# DDR4_MotherboardV2.net
KiCad netlist of a schematic drawn in Altium Designer
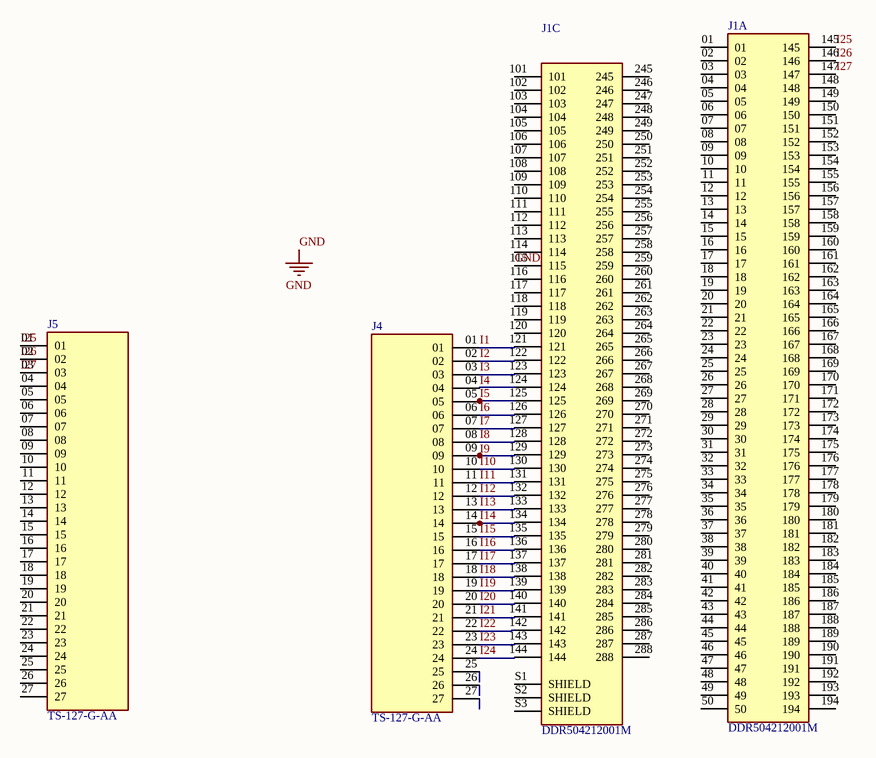
[diagram p0: DDR4_MotherboardV2.SchDoc]

(export (version "E")
  (design (tool "Eeschema 10.0.6"))
  (components
    (comp (ref "J1")
      (value "DDR504212001M")
      (footprint "AMPHENOL_DDR504212001M")
      (fields (field (name "MF") "Amphenol FCI"))
      (libsource (lib "Roberto SDSU") (part "DDR504212001M"))
    )
    (comp (ref "J4")
      (value "TS-127-G-AA")
      (footprint "SAMTEC_TS-127-G-AA")
      (description "Connector Header position")
      (fields (field (name "MF") "Samtec"))
      (libsource (lib "") (part "TS-127-G-AA_1"))
    )
    (comp (ref "J5")
      (value "TS-127-G-AA")
      (footprint "SAMTEC_TS-127-G-AA")
      (description "Connector Header position")
      (fields (field (name "MF") "Samtec"))
      (libsource (lib "Roberto SDSU") (part "TS-127-G-AA"))
    )
  )
  (nets
    (net (code "1") (name "/I1") (class "Default")
      (node (ref "J1") (pin "121") (pinfunction "121_121") (pintype "passive"))
      (node (ref "J4") (pin "01") (pinfunction "01_01") (pintype "passive"))
    )
    (net (code "2") (name "/I2") (class "Default")
      (node (ref "J1") (pin "122") (pinfunction "122_122") (pintype "passive"))
      (node (ref "J4") (pin "02") (pinfunction "02_02") (pintype "passive"))
    )
    (net (code "3") (name "/I3") (class "Default")
      (node (ref "J1") (pin "123") (pinfunction "123_123") (pintype "passive"))
      (node (ref "J4") (pin "03") (pinfunction "03_03") (pintype "passive"))
    )
    (net (code "4") (name "/I4") (class "Default")
      (node (ref "J1") (pin "124") (pinfunction "124_124") (pintype "passive"))
      (node (ref "J4") (pin "04") (pinfunction "04_04") (pintype "passive"))
    )
    (net (code "5") (name "/I5") (class "Default")
      (node (ref "J1") (pin "125") (pinfunction "125_125") (pintype "passive"))
      (node (ref "J4") (pin "05") (pinfunction "05_05") (pintype "passive"))
    )
    (net (code "6") (name "/I6") (class "Default")
      (node (ref "J1") (pin "126") (pinfunction "126_126") (pintype "passive"))
      (node (ref "J4") (pin "06") (pinfunction "06_06") (pintype "passive"))
    )
    (net (code "7") (name "/I7") (class "Default")
      (node (ref "J1") (pin "127") (pinfunction "127_127") (pintype "passive"))
      (node (ref "J4") (pin "07") (pinfunction "07_07") (pintype "passive"))
    )
    (net (code "8") (name "/I8") (class "Default")
      (node (ref "J1") (pin "128") (pinfunction "128_128") (pintype "passive"))
      (node (ref "J4") (pin "08") (pinfunction "08_08") (pintype "passive"))
    )
    (net (code "9") (name "/I9") (class "Default")
      (node (ref "J1") (pin "129") (pinfunction "129_129") (pintype "passive"))
      (node (ref "J4") (pin "09") (pinfunction "09_09") (pintype "passive"))
    )
    (net (code "10") (name "/I10") (class "Default")
      (node (ref "J1") (pin "130") (pinfunction "130_130") (pintype "passive"))
      (node (ref "J4") (pin "10") (pinfunction "10_10") (pintype "passive"))
    )
    (net (code "11") (name "/I11") (class "Default")
      (node (ref "J1") (pin "131") (pinfunction "131_131") (pintype "passive"))
      (node (ref "J4") (pin "11") (pinfunction "11_11") (pintype "passive"))
    )
    (net (code "12") (name "/I12") (class "Default")
      (node (ref "J1") (pin "132") (pinfunction "132_132") (pintype "passive"))
      (node (ref "J4") (pin "12") (pinfunction "12_12") (pintype "passive"))
    )
    (net (code "13") (name "/I13") (class "Default")
      (node (ref "J1") (pin "133") (pinfunction "133_133") (pintype "passive"))
      (node (ref "J4") (pin "13") (pinfunction "13_13") (pintype "passive"))
    )
    (net (code "14") (name "/I14") (class "Default")
      (node (ref "J1") (pin "134") (pinfunction "134_134") (pintype "passive"))
      (node (ref "J4") (pin "14") (pinfunction "14_14") (pintype "passive"))
    )
    (net (code "15") (name "/I15") (class "Default")
      (node (ref "J1") (pin "135") (pinfunction "135_135") (pintype "passive"))
      (node (ref "J4") (pin "15") (pinfunction "15_15") (pintype "passive"))
    )
    (net (code "16") (name "/I16") (class "Default")
      (node (ref "J1") (pin "136") (pinfunction "136_136") (pintype "passive"))
      (node (ref "J4") (pin "16") (pinfunction "16_16") (pintype "passive"))
    )
    (net (code "17") (name "/I17") (class "Default")
      (node (ref "J1") (pin "137") (pinfunction "137_137") (pintype "passive"))
      (node (ref "J4") (pin "17") (pinfunction "17_17") (pintype "passive"))
    )
    (net (code "18") (name "/I18") (class "Default")
      (node (ref "J1") (pin "138") (pinfunction "138_138") (pintype "passive"))
      (node (ref "J4") (pin "18") (pinfunction "18_18") (pintype "passive"))
    )
    (net (code "19") (name "/I19") (class "Default")
      (node (ref "J1") (pin "139") (pinfunction "139_139") (pintype "passive"))
      (node (ref "J4") (pin "19") (pinfunction "19_19") (pintype "passive"))
    )
    (net (code "20") (name "/I20") (class "Default")
      (node (ref "J1") (pin "140") (pinfunction "140_140") (pintype "passive"))
      (node (ref "J4") (pin "20") (pinfunction "20_20") (pintype "passive"))
    )
    (net (code "21") (name "/I21") (class "Default")
      (node (ref "J1") (pin "141") (pinfunction "141_141") (pintype "passive"))
      (node (ref "J4") (pin "21") (pinfunction "21_21") (pintype "passive"))
    )
    (net (code "22") (name "/I22") (class "Default")
      (node (ref "J1") (pin "142") (pinfunction "142_142") (pintype "passive"))
      (node (ref "J4") (pin "22") (pinfunction "22_22") (pintype "passive"))
    )
    (net (code "23") (name "/I23") (class "Default")
      (node (ref "J1") (pin "143") (pinfunction "143_143") (pintype "passive"))
      (node (ref "J4") (pin "23") (pinfunction "23_23") (pintype "passive"))
    )
    (net (code "24") (name "/I24") (class "Default")
      (node (ref "J1") (pin "144") (pinfunction "144_144") (pintype "passive"))
      (node (ref "J4") (pin "24") (pinfunction "24_24") (pintype "passive"))
    )
    (net (code "25") (name "/I25") (class "Default")
      (node (ref "J1") (pin "145") (pinfunction "145_145") (pintype "passive"))
      (node (ref "J5") (pin "01") (pinfunction "01_01") (pintype "passive"))
    )
    (net (code "26") (name "/I26") (class "Default")
      (node (ref "J1") (pin "146") (pinfunction "146_146") (pintype "passive"))
      (node (ref "J5") (pin "02") (pinfunction "02_02") (pintype "passive"))
    )
    (net (code "27") (name "/I27") (class "Default")
      (node (ref "J1") (pin "147") (pinfunction "147_147") (pintype "passive"))
      (node (ref "J5") (pin "03") (pinfunction "03_03") (pintype "passive"))
    )
    (net (code "28") (name "GND") (class "Default")
      (node (ref "J1") (pin "115") (pinfunction "115_115") (pintype "passive"))
    )
    (net (code "29") (name "unconnected-(J1-Pad01)") (class "Default")
      (node (ref "J1") (pin "01") (pinfunction "01_01") (pintype "passive"))
    )
    (net (code "30") (name "unconnected-(J1-Pad02)") (class "Default")
      (node (ref "J1") (pin "02") (pinfunction "02_02") (pintype "passive"))
    )
    (net (code "31") (name "unconnected-(J1-Pad03)") (class "Default")
      (node (ref "J1") (pin "03") (pinfunction "03_03") (pintype "passive"))
    )
    (net (code "32") (name "unconnected-(J1-Pad04)") (class "Default")
      (node (ref "J1") (pin "04") (pinfunction "04_04") (pintype "passive"))
    )
    (net (code "33") (name "unconnected-(J1-Pad05)") (class "Default")
      (node (ref "J1") (pin "05") (pinfunction "05_05") (pintype "passive"))
    )
    (net (code "34") (name "unconnected-(J1-Pad06)") (class "Default")
      (node (ref "J1") (pin "06") (pinfunction "06_06") (pintype "passive"))
    )
    (net (code "35") (name "unconnected-(J1-Pad07)") (class "Default")
      (node (ref "J1") (pin "07") (pinfunction "07_07") (pintype "passive"))
    )
    (net (code "36") (name "unconnected-(J1-Pad08)") (class "Default")
      (node (ref "J1") (pin "08") (pinfunction "08_08") (pintype "passive"))
    )
    (net (code "37") (name "unconnected-(J1-Pad09)") (class "Default")
      (node (ref "J1") (pin "09") (pinfunction "09_09") (pintype "passive"))
    )
    (net (code "38") (name "unconnected-(J1-Pad10)") (class "Default")
      (node (ref "J1") (pin "10") (pinfunction "10_10") (pintype "passive"))
    )
    (net (code "39") (name "unconnected-(J1-Pad11)") (class "Default")
      (node (ref "J1") (pin "11") (pinfunction "11_11") (pintype "passive"))
    )
    (net (code "40") (name "unconnected-(J1-Pad12)") (class "Default")
      (node (ref "J1") (pin "12") (pinfunction "12_12") (pintype "passive"))
    )
    (net (code "41") (name "unconnected-(J1-Pad13)") (class "Default")
      (node (ref "J1") (pin "13") (pinfunction "13_13") (pintype "passive"))
    )
    (net (code "42") (name "unconnected-(J1-Pad14)") (class "Default")
      (node (ref "J1") (pin "14") (pinfunction "14_14") (pintype "passive"))
    )
    (net (code "43") (name "unconnected-(J1-Pad15)") (class "Default")
      (node (ref "J1") (pin "15") (pinfunction "15_15") (pintype "passive"))
    )
    (net (code "44") (name "unconnected-(J1-Pad16)") (class "Default")
      (node (ref "J1") (pin "16") (pinfunction "16_16") (pintype "passive"))
    )
    (net (code "45") (name "unconnected-(J1-Pad17)") (class "Default")
      (node (ref "J1") (pin "17") (pinfunction "17_17") (pintype "passive"))
    )
    (net (code "46") (name "unconnected-(J1-Pad18)") (class "Default")
      (node (ref "J1") (pin "18") (pinfunction "18_18") (pintype "passive"))
    )
    (net (code "47") (name "unconnected-(J1-Pad19)") (class "Default")
      (node (ref "J1") (pin "19") (pinfunction "19_19") (pintype "passive"))
    )
    (net (code "48") (name "unconnected-(J1-Pad20)") (class "Default")
      (node (ref "J1") (pin "20") (pinfunction "20_20") (pintype "passive"))
    )
    (net (code "49") (name "unconnected-(J1-Pad21)") (class "Default")
      (node (ref "J1") (pin "21") (pinfunction "21_21") (pintype "passive"))
    )
    (net (code "50") (name "unconnected-(J1-Pad22)") (class "Default")
      (node (ref "J1") (pin "22") (pinfunction "22_22") (pintype "passive"))
    )
    (net (code "51") (name "unconnected-(J1-Pad23)") (class "Default")
      (node (ref "J1") (pin "23") (pinfunction "23_23") (pintype "passive"))
    )
    (net (code "52") (name "unconnected-(J1-Pad24)") (class "Default")
      (node (ref "J1") (pin "24") (pinfunction "24_24") (pintype "passive"))
    )
    (net (code "53") (name "unconnected-(J1-Pad25)") (class "Default")
      (node (ref "J1") (pin "25") (pinfunction "25_25") (pintype "passive"))
    )
    (net (code "54") (name "unconnected-(J1-Pad26)") (class "Default")
      (node (ref "J1") (pin "26") (pinfunction "26_26") (pintype "passive"))
    )
    (net (code "55") (name "unconnected-(J1-Pad27)") (class "Default")
      (node (ref "J1") (pin "27") (pinfunction "27_27") (pintype "passive"))
    )
    (net (code "56") (name "unconnected-(J1-Pad28)") (class "Default")
      (node (ref "J1") (pin "28") (pinfunction "28_28") (pintype "passive"))
    )
    (net (code "57") (name "unconnected-(J1-Pad29)") (class "Default")
      (node (ref "J1") (pin "29") (pinfunction "29_29") (pintype "passive"))
    )
    (net (code "58") (name "unconnected-(J1-Pad30)") (class "Default")
      (node (ref "J1") (pin "30") (pinfunction "30_30") (pintype "passive"))
    )
    (net (code "59") (name "unconnected-(J1-Pad31)") (class "Default")
      (node (ref "J1") (pin "31") (pinfunction "31_31") (pintype "passive"))
    )
    (net (code "60") (name "unconnected-(J1-Pad32)") (class "Default")
      (node (ref "J1") (pin "32") (pinfunction "32_32") (pintype "passive"))
    )
    (net (code "61") (name "unconnected-(J1-Pad33)") (class "Default")
      (node (ref "J1") (pin "33") (pinfunction "33_33") (pintype "passive"))
    )
    (net (code "62") (name "unconnected-(J1-Pad34)") (class "Default")
      (node (ref "J1") (pin "34") (pinfunction "34_34") (pintype "passive"))
    )
    (net (code "63") (name "unconnected-(J1-Pad35)") (class "Default")
      (node (ref "J1") (pin "35") (pinfunction "35_35") (pintype "passive"))
    )
    (net (code "64") (name "unconnected-(J1-Pad36)") (class "Default")
      (node (ref "J1") (pin "36") (pinfunction "36_36") (pintype "passive"))
    )
    (net (code "65") (name "unconnected-(J1-Pad37)") (class "Default")
      (node (ref "J1") (pin "37") (pinfunction "37_37") (pintype "passive"))
    )
    (net (code "66") (name "unconnected-(J1-Pad38)") (class "Default")
      (node (ref "J1") (pin "38") (pinfunction "38_38") (pintype "passive"))
    )
    (net (code "67") (name "unconnected-(J1-Pad39)") (class "Default")
      (node (ref "J1") (pin "39") (pinfunction "39_39") (pintype "passive"))
    )
    (net (code "68") (name "unconnected-(J1-Pad40)") (class "Default")
      (node (ref "J1") (pin "40") (pinfunction "40_40") (pintype "passive"))
    )
    (net (code "69") (name "unconnected-(J1-Pad41)") (class "Default")
      (node (ref "J1") (pin "41") (pinfunction "41_41") (pintype "passive"))
    )
    (net (code "70") (name "unconnected-(J1-Pad42)") (class "Default")
      (node (ref "J1") (pin "42") (pinfunction "42_42") (pintype "passive"))
    )
    (net (code "71") (name "unconnected-(J1-Pad43)") (class "Default")
      (node (ref "J1") (pin "43") (pinfunction "43_43") (pintype "passive"))
    )
    (net (code "72") (name "unconnected-(J1-Pad44)") (class "Default")
      (node (ref "J1") (pin "44") (pinfunction "44_44") (pintype "passive"))
    )
    (net (code "73") (name "unconnected-(J1-Pad45)") (class "Default")
      (node (ref "J1") (pin "45") (pinfunction "45_45") (pintype "passive"))
    )
    (net (code "74") (name "unconnected-(J1-Pad46)") (class "Default")
      (node (ref "J1") (pin "46") (pinfunction "46_46") (pintype "passive"))
    )
    (net (code "75") (name "unconnected-(J1-Pad47)") (class "Default")
      (node (ref "J1") (pin "47") (pinfunction "47_47") (pintype "passive"))
    )
    (net (code "76") (name "unconnected-(J1-Pad48)") (class "Default")
      (node (ref "J1") (pin "48") (pinfunction "48_48") (pintype "passive"))
    )
    (net (code "77") (name "unconnected-(J1-Pad49)") (class "Default")
      (node (ref "J1") (pin "49") (pinfunction "49_49") (pintype "passive"))
    )
    (net (code "78") (name "unconnected-(J1-Pad50)") (class "Default")
      (node (ref "J1") (pin "50") (pinfunction "50_50") (pintype "passive"))
    )
    (net (code "79") (name "unconnected-(J1-Pad101)") (class "Default")
      (node (ref "J1") (pin "101") (pinfunction "101_101") (pintype "passive"))
    )
    (net (code "80") (name "unconnected-(J1-Pad102)") (class "Default")
      (node (ref "J1") (pin "102") (pinfunction "102_102") (pintype "passive"))
    )
    (net (code "81") (name "unconnected-(J1-Pad103)") (class "Default")
      (node (ref "J1") (pin "103") (pinfunction "103_103") (pintype "passive"))
    )
    (net (code "82") (name "unconnected-(J1-Pad104)") (class "Default")
      (node (ref "J1") (pin "104") (pinfunction "104_104") (pintype "passive"))
    )
    (net (code "83") (name "unconnected-(J1-Pad105)") (class "Default")
      (node (ref "J1") (pin "105") (pinfunction "105_105") (pintype "passive"))
    )
    (net (code "84") (name "unconnected-(J1-Pad106)") (class "Default")
      (node (ref "J1") (pin "106") (pinfunction "106_106") (pintype "passive"))
    )
    (net (code "85") (name "unconnected-(J1-Pad107)") (class "Default")
      (node (ref "J1") (pin "107") (pinfunction "107_107") (pintype "passive"))
    )
    (net (code "86") (name "unconnected-(J1-Pad108)") (class "Default")
      (node (ref "J1") (pin "108") (pinfunction "108_108") (pintype "passive"))
    )
    (net (code "87") (name "unconnected-(J1-Pad109)") (class "Default")
      (node (ref "J1") (pin "109") (pinfunction "109_109") (pintype "passive"))
    )
    (net (code "88") (name "unconnected-(J1-Pad110)") (class "Default")
      (node (ref "J1") (pin "110") (pinfunction "110_110") (pintype "passive"))
    )
    (net (code "89") (name "unconnected-(J1-Pad111)") (class "Default")
      (node (ref "J1") (pin "111") (pinfunction "111_111") (pintype "passive"))
    )
    (net (code "90") (name "unconnected-(J1-Pad112)") (class "Default")
      (node (ref "J1") (pin "112") (pinfunction "112_112") (pintype "passive"))
    )
    (net (code "91") (name "unconnected-(J1-Pad113)") (class "Default")
      (node (ref "J1") (pin "113") (pinfunction "113_113") (pintype "passive"))
    )
    (net (code "92") (name "unconnected-(J1-Pad114)") (class "Default")
      (node (ref "J1") (pin "114") (pinfunction "114_114") (pintype "passive"))
    )
    (net (code "93") (name "unconnected-(J1-Pad116)") (class "Default")
      (node (ref "J1") (pin "116") (pinfunction "116_116") (pintype "passive"))
    )
    (net (code "94") (name "unconnected-(J1-Pad117)") (class "Default")
      (node (ref "J1") (pin "117") (pinfunction "117_117") (pintype "passive"))
    )
    (net (code "95") (name "unconnected-(J1-Pad118)") (class "Default")
      (node (ref "J1") (pin "118") (pinfunction "118_118") (pintype "passive"))
    )
    (net (code "96") (name "unconnected-(J1-Pad119)") (class "Default")
      (node (ref "J1") (pin "119") (pinfunction "119_119") (pintype "passive"))
    )
    (net (code "97") (name "unconnected-(J1-Pad120)") (class "Default")
      (node (ref "J1") (pin "120") (pinfunction "120_120") (pintype "passive"))
    )
    (net (code "98") (name "unconnected-(J1-Pad148)") (class "Default")
      (node (ref "J1") (pin "148") (pinfunction "148_148") (pintype "passive"))
    )
    (net (code "99") (name "unconnected-(J1-Pad149)") (class "Default")
      (node (ref "J1") (pin "149") (pinfunction "149_149") (pintype "passive"))
    )
    (net (code "100") (name "unconnected-(J1-Pad150)") (class "Default")
      (node (ref "J1") (pin "150") (pinfunction "150_150") (pintype "passive"))
    )
    (net (code "101") (name "unconnected-(J1-Pad151)") (class "Default")
      (node (ref "J1") (pin "151") (pinfunction "151_151") (pintype "passive"))
    )
    (net (code "102") (name "unconnected-(J1-Pad152)") (class "Default")
      (node (ref "J1") (pin "152") (pinfunction "152_152") (pintype "passive"))
    )
    (net (code "103") (name "unconnected-(J1-Pad153)") (class "Default")
      (node (ref "J1") (pin "153") (pinfunction "153_153") (pintype "passive"))
    )
    (net (code "104") (name "unconnected-(J1-Pad154)") (class "Default")
      (node (ref "J1") (pin "154") (pinfunction "154_154") (pintype "passive"))
    )
    (net (code "105") (name "unconnected-(J1-Pad155)") (class "Default")
      (node (ref "J1") (pin "155") (pinfunction "155_155") (pintype "passive"))
    )
    (net (code "106") (name "unconnected-(J1-Pad156)") (class "Default")
      (node (ref "J1") (pin "156") (pinfunction "156_156") (pintype "passive"))
    )
    (net (code "107") (name "unconnected-(J1-Pad157)") (class "Default")
      (node (ref "J1") (pin "157") (pinfunction "157_157") (pintype "passive"))
    )
    (net (code "108") (name "unconnected-(J1-Pad158)") (class "Default")
      (node (ref "J1") (pin "158") (pinfunction "158_158") (pintype "passive"))
    )
    (net (code "109") (name "unconnected-(J1-Pad159)") (class "Default")
      (node (ref "J1") (pin "159") (pinfunction "159_159") (pintype "passive"))
    )
    (net (code "110") (name "unconnected-(J1-Pad160)") (class "Default")
      (node (ref "J1") (pin "160") (pinfunction "160_160") (pintype "passive"))
    )
    (net (code "111") (name "unconnected-(J1-Pad161)") (class "Default")
      (node (ref "J1") (pin "161") (pinfunction "161_161") (pintype "passive"))
    )
    (net (code "112") (name "unconnected-(J1-Pad162)") (class "Default")
      (node (ref "J1") (pin "162") (pinfunction "162_162") (pintype "passive"))
    )
    (net (code "113") (name "unconnected-(J1-Pad163)") (class "Default")
      (node (ref "J1") (pin "163") (pinfunction "163_163") (pintype "passive"))
    )
    (net (code "114") (name "unconnected-(J1-Pad164)") (class "Default")
      (node (ref "J1") (pin "164") (pinfunction "164_164") (pintype "passive"))
    )
    (net (code "115") (name "unconnected-(J1-Pad165)") (class "Default")
      (node (ref "J1") (pin "165") (pinfunction "165_165") (pintype "passive"))
    )
    (net (code "116") (name "unconnected-(J1-Pad166)") (class "Default")
      (node (ref "J1") (pin "166") (pinfunction "166_166") (pintype "passive"))
    )
    (net (code "117") (name "unconnected-(J1-Pad167)") (class "Default")
      (node (ref "J1") (pin "167") (pinfunction "167_167") (pintype "passive"))
    )
    (net (code "118") (name "unconnected-(J1-Pad168)") (class "Default")
      (node (ref "J1") (pin "168") (pinfunction "168_168") (pintype "passive"))
    )
    (net (code "119") (name "unconnected-(J1-Pad169)") (class "Default")
      (node (ref "J1") (pin "169") (pinfunction "169_169") (pintype "passive"))
    )
    (net (code "120") (name "unconnected-(J1-Pad170)") (class "Default")
      (node (ref "J1") (pin "170") (pinfunction "170_170") (pintype "passive"))
    )
    (net (code "121") (name "unconnected-(J1-Pad171)") (class "Default")
      (node (ref "J1") (pin "171") (pinfunction "171_171") (pintype "passive"))
    )
    (net (code "122") (name "unconnected-(J1-Pad172)") (class "Default")
      (node (ref "J1") (pin "172") (pinfunction "172_172") (pintype "passive"))
    )
    (net (code "123") (name "unconnected-(J1-Pad173)") (class "Default")
      (node (ref "J1") (pin "173") (pinfunction "173_173") (pintype "passive"))
    )
    (net (code "124") (name "unconnected-(J1-Pad174)") (class "Default")
      (node (ref "J1") (pin "174") (pinfunction "174_174") (pintype "passive"))
    )
    (net (code "125") (name "unconnected-(J1-Pad175)") (class "Default")
      (node (ref "J1") (pin "175") (pinfunction "175_175") (pintype "passive"))
    )
    (net (code "126") (name "unconnected-(J1-Pad176)") (class "Default")
      (node (ref "J1") (pin "176") (pinfunction "176_176") (pintype "passive"))
    )
    (net (code "127") (name "unconnected-(J1-Pad177)") (class "Default")
      (node (ref "J1") (pin "177") (pinfunction "177_177") (pintype "passive"))
    )
    (net (code "128") (name "unconnected-(J1-Pad178)") (class "Default")
      (node (ref "J1") (pin "178") (pinfunction "178_178") (pintype "passive"))
    )
    (net (code "129") (name "unconnected-(J1-Pad179)") (class "Default")
      (node (ref "J1") (pin "179") (pinfunction "179_179") (pintype "passive"))
    )
    (net (code "130") (name "unconnected-(J1-Pad180)") (class "Default")
      (node (ref "J1") (pin "180") (pinfunction "180_180") (pintype "passive"))
    )
    (net (code "131") (name "unconnected-(J1-Pad181)") (class "Default")
      (node (ref "J1") (pin "181") (pinfunction "181_181") (pintype "passive"))
    )
    (net (code "132") (name "unconnected-(J1-Pad182)") (class "Default")
      (node (ref "J1") (pin "182") (pinfunction "182_182") (pintype "passive"))
    )
    (net (code "133") (name "unconnected-(J1-Pad183)") (class "Default")
      (node (ref "J1") (pin "183") (pinfunction "183_183") (pintype "passive"))
    )
    (net (code "134") (name "unconnected-(J1-Pad184)") (class "Default")
      (node (ref "J1") (pin "184") (pinfunction "184_184") (pintype "passive"))
    )
    (net (code "135") (name "unconnected-(J1-Pad185)") (class "Default")
      (node (ref "J1") (pin "185") (pinfunction "185_185") (pintype "passive"))
    )
    (net (code "136") (name "unconnected-(J1-Pad186)") (class "Default")
      (node (ref "J1") (pin "186") (pinfunction "186_186") (pintype "passive"))
    )
    (net (code "137") (name "unconnected-(J1-Pad187)") (class "Default")
      (node (ref "J1") (pin "187") (pinfunction "187_187") (pintype "passive"))
    )
    (net (code "138") (name "unconnected-(J1-Pad188)") (class "Default")
      (node (ref "J1") (pin "188") (pinfunction "188_188") (pintype "passive"))
    )
    (net (code "139") (name "unconnected-(J1-Pad189)") (class "Default")
      (node (ref "J1") (pin "189") (pinfunction "189_189") (pintype "passive"))
    )
    (net (code "140") (name "unconnected-(J1-Pad190)") (class "Default")
      (node (ref "J1") (pin "190") (pinfunction "190_190") (pintype "passive"))
    )
    (net (code "141") (name "unconnected-(J1-Pad191)") (class "Default")
      (node (ref "J1") (pin "191") (pinfunction "191_191") (pintype "passive"))
    )
    (net (code "142") (name "unconnected-(J1-Pad192)") (class "Default")
      (node (ref "J1") (pin "192") (pinfunction "192_192") (pintype "passive"))
    )
    (net (code "143") (name "unconnected-(J1-Pad193)") (class "Default")
      (node (ref "J1") (pin "193") (pinfunction "193_193") (pintype "passive"))
    )
    (net (code "144") (name "unconnected-(J1-Pad194)") (class "Default")
      (node (ref "J1") (pin "194") (pinfunction "194_194") (pintype "passive"))
    )
    (net (code "145") (name "unconnected-(J1-Pad245)") (class "Default")
      (node (ref "J1") (pin "245") (pinfunction "245_245") (pintype "passive"))
    )
    (net (code "146") (name "unconnected-(J1-Pad246)") (class "Default")
      (node (ref "J1") (pin "246") (pinfunction "246_246") (pintype "passive"))
    )
    (net (code "147") (name "unconnected-(J1-Pad247)") (class "Default")
      (node (ref "J1") (pin "247") (pinfunction "247_247") (pintype "passive"))
    )
    (net (code "148") (name "unconnected-(J1-Pad248)") (class "Default")
      (node (ref "J1") (pin "248") (pinfunction "248_248") (pintype "passive"))
    )
    (net (code "149") (name "unconnected-(J1-Pad249)") (class "Default")
      (node (ref "J1") (pin "249") (pinfunction "249_249") (pintype "passive"))
    )
    (net (code "150") (name "unconnected-(J1-Pad250)") (class "Default")
      (node (ref "J1") (pin "250") (pinfunction "250_250") (pintype "passive"))
    )
    (net (code "151") (name "unconnected-(J1-Pad251)") (class "Default")
      (node (ref "J1") (pin "251") (pinfunction "251_251") (pintype "passive"))
    )
    (net (code "152") (name "unconnected-(J1-Pad252)") (class "Default")
      (node (ref "J1") (pin "252") (pinfunction "252_252") (pintype "passive"))
    )
    (net (code "153") (name "unconnected-(J1-Pad253)") (class "Default")
      (node (ref "J1") (pin "253") (pinfunction "253_253") (pintype "passive"))
    )
    (net (code "154") (name "unconnected-(J1-Pad254)") (class "Default")
      (node (ref "J1") (pin "254") (pinfunction "254_254") (pintype "passive"))
    )
    (net (code "155") (name "unconnected-(J1-Pad255)") (class "Default")
      (node (ref "J1") (pin "255") (pinfunction "255_255") (pintype "passive"))
    )
    (net (code "156") (name "unconnected-(J1-Pad256)") (class "Default")
      (node (ref "J1") (pin "256") (pinfunction "256_256") (pintype "passive"))
    )
    (net (code "157") (name "unconnected-(J1-Pad257)") (class "Default")
      (node (ref "J1") (pin "257") (pinfunction "257_257") (pintype "passive"))
    )
    (net (code "158") (name "unconnected-(J1-Pad258)") (class "Default")
      (node (ref "J1") (pin "258") (pinfunction "258_258") (pintype "passive"))
    )
    (net (code "159") (name "unconnected-(J1-Pad259)") (class "Default")
      (node (ref "J1") (pin "259") (pinfunction "259_259") (pintype "passive"))
    )
    (net (code "160") (name "unconnected-(J1-Pad260)") (class "Default")
      (node (ref "J1") (pin "260") (pinfunction "260_260") (pintype "passive"))
    )
    (net (code "161") (name "unconnected-(J1-Pad261)") (class "Default")
      (node (ref "J1") (pin "261") (pinfunction "261_261") (pintype "passive"))
    )
    (net (code "162") (name "unconnected-(J1-Pad262)") (class "Default")
      (node (ref "J1") (pin "262") (pinfunction "262_262") (pintype "passive"))
    )
    (net (code "163") (name "unconnected-(J1-Pad263)") (class "Default")
      (node (ref "J1") (pin "263") (pinfunction "263_263") (pintype "passive"))
    )
    (net (code "164") (name "unconnected-(J1-Pad264)") (class "Default")
      (node (ref "J1") (pin "264") (pinfunction "264_264") (pintype "passive"))
    )
    (net (code "165") (name "unconnected-(J1-Pad265)") (class "Default")
      (node (ref "J1") (pin "265") (pinfunction "265_265") (pintype "passive"))
    )
    (net (code "166") (name "unconnected-(J1-Pad266)") (class "Default")
      (node (ref "J1") (pin "266") (pinfunction "266_266") (pintype "passive"))
    )
    (net (code "167") (name "unconnected-(J1-Pad267)") (class "Default")
      (node (ref "J1") (pin "267") (pinfunction "267_267") (pintype "passive"))
    )
    (net (code "168") (name "unconnected-(J1-Pad268)") (class "Default")
      (node (ref "J1") (pin "268") (pinfunction "268_268") (pintype "passive"))
    )
    (net (code "169") (name "unconnected-(J1-Pad269)") (class "Default")
      (node (ref "J1") (pin "269") (pinfunction "269_269") (pintype "passive"))
    )
    (net (code "170") (name "unconnected-(J1-Pad270)") (class "Default")
      (node (ref "J1") (pin "270") (pinfunction "270_270") (pintype "passive"))
    )
    (net (code "171") (name "unconnected-(J1-Pad271)") (class "Default")
      (node (ref "J1") (pin "271") (pinfunction "271_271") (pintype "passive"))
    )
    (net (code "172") (name "unconnected-(J1-Pad272)") (class "Default")
      (node (ref "J1") (pin "272") (pinfunction "272_272") (pintype "passive"))
    )
    (net (code "173") (name "unconnected-(J1-Pad273)") (class "Default")
      (node (ref "J1") (pin "273") (pinfunction "273_273") (pintype "passive"))
    )
    (net (code "174") (name "unconnected-(J1-Pad274)") (class "Default")
      (node (ref "J1") (pin "274") (pinfunction "274_274") (pintype "passive"))
    )
    (net (code "175") (name "unconnected-(J1-Pad275)") (class "Default")
      (node (ref "J1") (pin "275") (pinfunction "275_275") (pintype "passive"))
    )
    (net (code "176") (name "unconnected-(J1-Pad276)") (class "Default")
      (node (ref "J1") (pin "276") (pinfunction "276_276") (pintype "passive"))
    )
    (net (code "177") (name "unconnected-(J1-Pad277)") (class "Default")
      (node (ref "J1") (pin "277") (pinfunction "277_277") (pintype "passive"))
    )
    (net (code "178") (name "unconnected-(J1-Pad278)") (class "Default")
      (node (ref "J1") (pin "278") (pinfunction "278_278") (pintype "passive"))
    )
    (net (code "179") (name "unconnected-(J1-Pad279)") (class "Default")
      (node (ref "J1") (pin "279") (pinfunction "279_279") (pintype "passive"))
    )
    (net (code "180") (name "unconnected-(J1-Pad280)") (class "Default")
      (node (ref "J1") (pin "280") (pinfunction "280_280") (pintype "passive"))
    )
    (net (code "181") (name "unconnected-(J1-Pad281)") (class "Default")
      (node (ref "J1") (pin "281") (pinfunction "281_281") (pintype "passive"))
    )
    (net (code "182") (name "unconnected-(J1-Pad282)") (class "Default")
      (node (ref "J1") (pin "282") (pinfunction "282_282") (pintype "passive"))
    )
    (net (code "183") (name "unconnected-(J1-Pad283)") (class "Default")
      (node (ref "J1") (pin "283") (pinfunction "283_283") (pintype "passive"))
    )
    (net (code "184") (name "unconnected-(J1-Pad284)") (class "Default")
      (node (ref "J1") (pin "284") (pinfunction "284_284") (pintype "passive"))
    )
    (net (code "185") (name "unconnected-(J1-Pad285)") (class "Default")
      (node (ref "J1") (pin "285") (pinfunction "285_285") (pintype "passive"))
    )
    (net (code "186") (name "unconnected-(J1-Pad286)") (class "Default")
      (node (ref "J1") (pin "286") (pinfunction "286_286") (pintype "passive"))
    )
    (net (code "187") (name "unconnected-(J1-Pad287)") (class "Default")
      (node (ref "J1") (pin "287") (pinfunction "287_287") (pintype "passive"))
    )
    (net (code "188") (name "unconnected-(J1-Pad288)") (class "Default")
      (node (ref "J1") (pin "288") (pinfunction "288_288") (pintype "passive"))
    )
    (net (code "189") (name "unconnected-(J1C-SHIELD-PadS1)") (class "Default")
      (node (ref "J1") (pin "S1") (pinfunction "SHIELD_S1") (pintype "passive"))
    )
    (net (code "190") (name "unconnected-(J1C-SHIELD-PadS2)") (class "Default")
      (node (ref "J1") (pin "S2") (pinfunction "SHIELD_S2") (pintype "passive"))
    )
    (net (code "191") (name "unconnected-(J1C-SHIELD-PadS3)") (class "Default")
      (node (ref "J1") (pin "S3") (pinfunction "SHIELD_S3") (pintype "passive"))
    )
    (net (code "192") (name "unconnected-(J4-Pad25)") (class "Default")
      (node (ref "J4") (pin "25") (pinfunction "25_25") (pintype "passive"))
    )
    (net (code "193") (name "unconnected-(J4-Pad26)") (class "Default")
      (node (ref "J4") (pin "26") (pinfunction "26_26") (pintype "passive"))
    )
    (net (code "194") (name "unconnected-(J4-Pad27)") (class "Default")
      (node (ref "J4") (pin "27") (pinfunction "27_27") (pintype "passive"))
    )
    (net (code "195") (name "unconnected-(J5-Pad04)") (class "Default")
      (node (ref "J5") (pin "04") (pinfunction "04_04") (pintype "passive"))
    )
    (net (code "196") (name "unconnected-(J5-Pad05)") (class "Default")
      (node (ref "J5") (pin "05") (pinfunction "05_05") (pintype "passive"))
    )
    (net (code "197") (name "unconnected-(J5-Pad06)") (class "Default")
      (node (ref "J5") (pin "06") (pinfunction "06_06") (pintype "passive"))
    )
    (net (code "198") (name "unconnected-(J5-Pad07)") (class "Default")
      (node (ref "J5") (pin "07") (pinfunction "07_07") (pintype "passive"))
    )
    (net (code "199") (name "unconnected-(J5-Pad08)") (class "Default")
      (node (ref "J5") (pin "08") (pinfunction "08_08") (pintype "passive"))
    )
    (net (code "200") (name "unconnected-(J5-Pad09)") (class "Default")
      (node (ref "J5") (pin "09") (pinfunction "09_09") (pintype "passive"))
    )
    (net (code "201") (name "unconnected-(J5-Pad10)") (class "Default")
      (node (ref "J5") (pin "10") (pinfunction "10_10") (pintype "passive"))
    )
    (net (code "202") (name "unconnected-(J5-Pad11)") (class "Default")
      (node (ref "J5") (pin "11") (pinfunction "11_11") (pintype "passive"))
    )
    (net (code "203") (name "unconnected-(J5-Pad12)") (class "Default")
      (node (ref "J5") (pin "12") (pinfunction "12_12") (pintype "passive"))
    )
    (net (code "204") (name "unconnected-(J5-Pad13)") (class "Default")
      (node (ref "J5") (pin "13") (pinfunction "13_13") (pintype "passive"))
    )
    (net (code "205") (name "unconnected-(J5-Pad14)") (class "Default")
      (node (ref "J5") (pin "14") (pinfunction "14_14") (pintype "passive"))
    )
    (net (code "206") (name "unconnected-(J5-Pad15)") (class "Default")
      (node (ref "J5") (pin "15") (pinfunction "15_15") (pintype "passive"))
    )
    (net (code "207") (name "unconnected-(J5-Pad16)") (class "Default")
      (node (ref "J5") (pin "16") (pinfunction "16_16") (pintype "passive"))
    )
    (net (code "208") (name "unconnected-(J5-Pad17)") (class "Default")
      (node (ref "J5") (pin "17") (pinfunction "17_17") (pintype "passive"))
    )
    (net (code "209") (name "unconnected-(J5-Pad18)") (class "Default")
      (node (ref "J5") (pin "18") (pinfunction "18_18") (pintype "passive"))
    )
    (net (code "210") (name "unconnected-(J5-Pad19)") (class "Default")
      (node (ref "J5") (pin "19") (pinfunction "19_19") (pintype "passive"))
    )
    (net (code "211") (name "unconnected-(J5-Pad20)") (class "Default")
      (node (ref "J5") (pin "20") (pinfunction "20_20") (pintype "passive"))
    )
    (net (code "212") (name "unconnected-(J5-Pad21)") (class "Default")
      (node (ref "J5") (pin "21") (pinfunction "21_21") (pintype "passive"))
    )
    (net (code "213") (name "unconnected-(J5-Pad22)") (class "Default")
      (node (ref "J5") (pin "22") (pinfunction "22_22") (pintype "passive"))
    )
    (net (code "214") (name "unconnected-(J5-Pad23)") (class "Default")
      (node (ref "J5") (pin "23") (pinfunction "23_23") (pintype "passive"))
    )
    (net (code "215") (name "unconnected-(J5-Pad24)") (class "Default")
      (node (ref "J5") (pin "24") (pinfunction "24_24") (pintype "passive"))
    )
    (net (code "216") (name "unconnected-(J5-Pad25)") (class "Default")
      (node (ref "J5") (pin "25") (pinfunction "25_25") (pintype "passive"))
    )
    (net (code "217") (name "unconnected-(J5-Pad26)") (class "Default")
      (node (ref "J5") (pin "26") (pinfunction "26_26") (pintype "passive"))
    )
    (net (code "218") (name "unconnected-(J5-Pad27)") (class "Default")
      (node (ref "J5") (pin "27") (pinfunction "27_27") (pintype "passive"))
    )
  )
)
